# Alimentation.net
KiCad netlist of a schematic drawn in Altium Designer
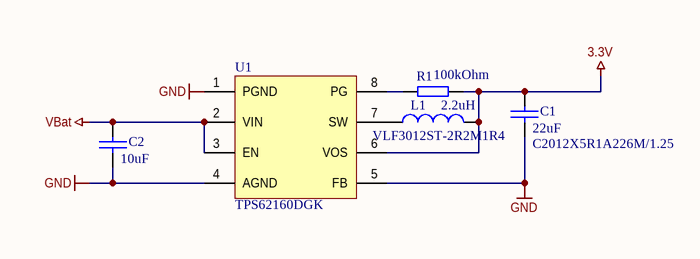
[diagram p0: Alimentation.SchDoc]

(export (version "E")
  (design (tool "Eeschema 10.0.6"))
  (components
    (comp (ref "C1")
      (value "C2012X5R1A226M/1.25")
      (footprint "080501")
      (description "CAPA")
      (fields (field (name "ALTIUM_VALUE") "22uF"))
      (libsource (lib "General-Sch-205") (part "CAPA"))
    )
    (comp (ref "C2")
      (value "10uF")
      (footprint "080501")
      (description "CAPA")
      (fields (field (name "Comment") "GRM21BR61E106KA73L"))
      (libsource (lib "General-Sch-205") (part "CAPA"))
    )
    (comp (ref "L1")
      (value "VLF3012ST-2R2M1R4")
      (footprint "080503")
      (fields (field (name "ALTIUM_VALUE") "2.2uH"))
      (libsource (lib "General-Sch-205") (part "INDUCTOR"))
    )
    (comp (ref "R1")
      (value "100kOhm")
      (footprint "080501")
      (fields (field (name "Comment") "ERJ-6GEYJ104V"))
      (libsource (lib "General-Sch-205") (part "RES"))
    )
    (comp (ref "U1")
      (value "TPS62160DGK")
      (footprint "TSOP65P490-8AM")
      (description "IC BUCK SYNC ADJ 1A 8MSOP")
      (libsource (lib "Schlib1") (part "TPS62160"))
    )
  )
  (nets
    (net (code "1") (name "3.3V") (class "Default")
      (node (ref "C1") (pin "1") (pintype "passive"))
      (node (ref "L1") (pin "2") (pintype "passive"))
      (node (ref "R1") (pin "2") (pintype "passive"))
      (node (ref "U1") (pin "6") (pinfunction "VOS_6") (pintype "passive"))
    )
    (net (code "2") (name "GND") (class "Default")
      (node (ref "C1") (pin "2") (pintype "passive"))
      (node (ref "C2") (pin "2") (pintype "passive"))
      (node (ref "U1") (pin "1") (pinfunction "PGND_1") (pintype "passive"))
      (node (ref "U1") (pin "4") (pinfunction "AGND_4") (pintype "passive"))
      (node (ref "U1") (pin "5") (pinfunction "FB_5") (pintype "passive"))
    )
    (net (code "3") (name "Net-(U1-PG)") (class "Default")
      (node (ref "R1") (pin "1") (pintype "passive"))
      (node (ref "U1") (pin "8") (pinfunction "PG_8") (pintype "passive"))
    )
    (net (code "4") (name "Net-(U1-SW)") (class "Default")
      (node (ref "L1") (pin "1") (pintype "passive"))
      (node (ref "U1") (pin "7") (pinfunction "SW_7") (pintype "passive"))
    )
    (net (code "5") (name "VBat") (class "Default")
      (node (ref "C2") (pin "1") (pintype "passive"))
      (node (ref "U1") (pin "2") (pinfunction "VIN_2") (pintype "passive"))
      (node (ref "U1") (pin "3") (pinfunction "EN_3") (pintype "passive"))
    )
  )
)
